# 1_AMS_Input_Stage.net
KiCad netlist of a schematic drawn in Altium Designer
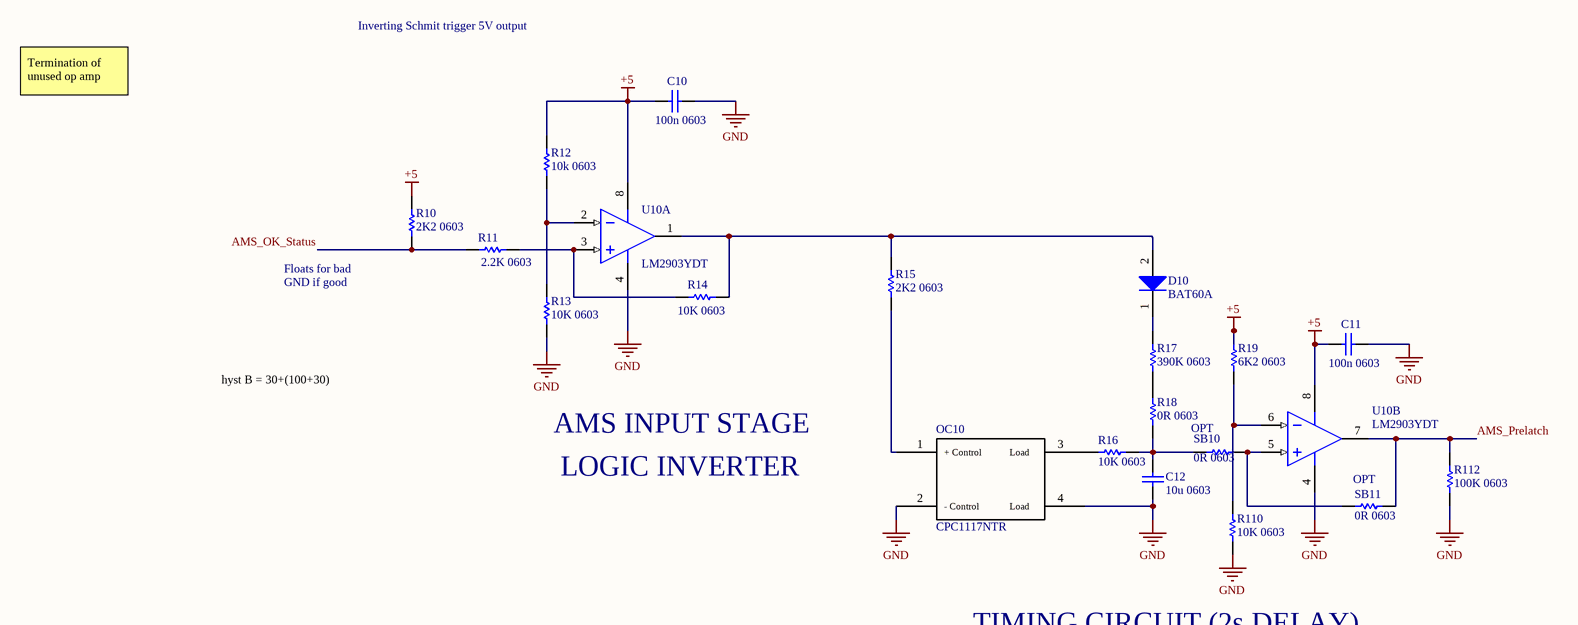
[diagram p0: [1] AMS_Input_Stage.SchDoc]

(export (version "E")
  (design (tool "Eeschema 10.0.6"))
  (components
    (comp (ref "C10")
      (value "100n 0603")
      (footprint "CAPC0603(1608)100_M")
      (description "Capacitor")
      (fields (field (name "PUBLISHER") "Altium Limited"))
      (libsource (lib "Miscellaneous Devices") (part "Cap"))
    )
    (comp (ref "C11")
      (value "100n 0603")
      (footprint "CAPC0603(1608)100_M")
      (description "Capacitor")
      (fields (field (name "PUBLISHER") "Altium Limited"))
      (libsource (lib "Miscellaneous Devices") (part "Cap"))
    )
    (comp (ref "C12")
      (value "10u 0603")
      (footprint "CAPC0603(1608)100_M")
      (description "Capacitor")
      (fields (field (name "PUBLISHER") "Altium Limited"))
      (libsource (lib "Miscellaneous Devices") (part "Cap"))
    )
    (comp (ref "D10")
      (value "BAT60A")
      (footprint "INF-SOD323_V")
      (description "Silicon Schottky Diode, -55 to 85 degC, SOD323, Reel, Green")
      (fields (field (name "MANUFACTURER") "Infineon"))
      (libsource (lib "Altium Content Vault") (part "INF-D_K1A2-2"))
    )
    (comp (ref "OC10")
      (value "CPC1117NTR")
      (footprint "SOP-4 (CPC1117NTR)")
      (libsource (lib "Schematic_Library_AMS_IMD") (part "CPC1117NTR"))
    )
    (comp (ref "R10")
      (value "2K2 0603")
      (footprint "CAPC0603(1608)100_M")
      (description "Resistor")
      (fields (field (name "PUBLISHER") "Altium Limited"))
      (libsource (lib "Miscellaneous Devices") (part "Res1"))
    )
    (comp (ref "R11")
      (value "2.2K 0603")
      (footprint "CAPC0603(1608)100_M")
      (description "Resistor")
      (fields (field (name "PUBLISHER") "Altium Limited"))
      (libsource (lib "Miscellaneous Devices") (part "Res1"))
    )
    (comp (ref "R12")
      (value "10k 0603")
      (footprint "CAPC0603(1608)100_M")
      (description "Resistor")
      (fields (field (name "PUBLISHER") "Altium Limited"))
      (libsource (lib "Miscellaneous Devices") (part "Res1"))
    )
    (comp (ref "R13")
      (value "10K 0603")
      (footprint "CAPC0603(1608)100_M")
      (description "Resistor")
      (fields (field (name "PUBLISHER") "Altium Limited"))
      (libsource (lib "Miscellaneous Devices") (part "Res1"))
    )
    (comp (ref "R14")
      (value "10K 0603")
      (footprint "CAPC0603(1608)100_M")
      (description "Resistor")
      (fields (field (name "PUBLISHER") "Altium Limited"))
      (libsource (lib "Miscellaneous Devices") (part "Res1"))
    )
    (comp (ref "R15")
      (value "2K2 0603")
      (footprint "CAPC0603(1608)100_M")
      (description "Resistor")
      (fields (field (name "PUBLISHER") "Altium Limited"))
      (libsource (lib "Miscellaneous Devices") (part "Res1"))
    )
    (comp (ref "R16")
      (value "10K 0603")
      (footprint "CAPC0603(1608)100_M")
      (description "Resistor")
      (fields (field (name "PUBLISHER") "Altium Limited"))
      (libsource (lib "Miscellaneous Devices") (part "Res1"))
    )
    (comp (ref "R17")
      (value "390K 0603")
      (footprint "CAPC0603(1608)100_M")
      (description "Resistor")
      (fields (field (name "PUBLISHER") "Altium Limited"))
      (libsource (lib "Miscellaneous Devices") (part "Res1"))
    )
    (comp (ref "R18")
      (value "0R 0603")
      (footprint "CAPC0603(1608)100_M")
      (description "Resistor")
      (fields (field (name "PUBLISHER") "Altium Limited"))
      (libsource (lib "Miscellaneous Devices") (part "Res1"))
    )
    (comp (ref "R19")
      (value "6K2 0603")
      (footprint "CAPC0603(1608)100_M")
      (description "Resistor")
      (fields (field (name "PUBLISHER") "Altium Limited"))
      (libsource (lib "Miscellaneous Devices") (part "Res1"))
    )
    (comp (ref "R110")
      (value "10K 0603")
      (footprint "CAPC0603(1608)100_M")
      (description "Resistor")
      (fields (field (name "PUBLISHER") "Altium Limited"))
      (libsource (lib "Miscellaneous Devices") (part "Res1"))
    )
    (comp (ref "R112")
      (value "100K 0603")
      (footprint "CAPC0603(1608)100_M")
      (description "Resistor")
      (fields (field (name "PUBLISHER") "Altium Limited"))
      (libsource (lib "Miscellaneous Devices") (part "Res1"))
    )
    (comp (ref "SB10")
      (value "0R 0603")
      (footprint "CAPC0603(1608)100_M")
      (description "Resistor")
      (fields (field (name "PUBLISHER") "Altium Limited"))
      (libsource (lib "Miscellaneous Devices") (part "Res1"))
    )
    (comp (ref "SB11")
      (value "0R 0603")
      (footprint "CAPC0603(1608)100_M")
      (description "Resistor")
      (fields (field (name "PUBLISHER") "Altium Limited"))
      (libsource (lib "Miscellaneous Devices") (part "Res1"))
    )
    (comp (ref "U10")
      (value "LM2903YDT")
      (footprint "ONSC-SOIC-8-751-07_V")
      (fields (field (name "MANUFACTURER") "On Semiconductor") (field (name "PARTNUMBER") "LM2903DR2G"))
      (libsource (lib "Altium Content Vault") (part "ONSC-LM2903X_X93_LMV393_NVC2903-8"))
    )
  )
  (nets
    (net (code "1") (name "+5") (class "Default")
      (node (ref "C10") (pin "1") (pinfunction "1_1") (pintype "passive"))
      (node (ref "C11") (pin "1") (pinfunction "1_1") (pintype "passive"))
      (node (ref "R10") (pin "1") (pinfunction "1_1") (pintype "passive"))
      (node (ref "R12") (pin "2") (pinfunction "2_2") (pintype "passive"))
      (node (ref "R19") (pin "1") (pinfunction "1_1") (pintype "passive"))
      (node (ref "U10") (pin "8") (pinfunction "VCC_8") (pintype "power_in"))
    )
    (net (code "2") (name "/AMS_OK_Status") (class "Default")
      (node (ref "R10") (pin "2") (pinfunction "2_2") (pintype "passive"))
      (node (ref "R11") (pin "1") (pinfunction "1_1") (pintype "passive"))
    )
    (net (code "3") (name "/AMS_Prelatch") (class "Default")
      (node (ref "R112") (pin "1") (pinfunction "1_1") (pintype "passive"))
      (node (ref "SB11") (pin "2") (pinfunction "2_2") (pintype "passive"))
      (node (ref "U10") (pin "7") (pinfunction "OUTB_7") (pintype "open_collector"))
    )
    (net (code "4") (name "GND") (class "Default")
      (node (ref "C10") (pin "2") (pinfunction "2_2") (pintype "passive"))
      (node (ref "C11") (pin "2") (pinfunction "2_2") (pintype "passive"))
      (node (ref "C12") (pin "2") (pinfunction "2_2") (pintype "passive"))
      (node (ref "OC10") (pin "2") (pinfunction "2_2") (pintype "passive"))
      (node (ref "OC10") (pin "4") (pinfunction "4_4") (pintype "passive"))
      (node (ref "R110") (pin "2") (pinfunction "2_2") (pintype "passive"))
      (node (ref "R112") (pin "2") (pinfunction "2_2") (pintype "passive"))
      (node (ref "R13") (pin "1") (pinfunction "1_1") (pintype "passive"))
      (node (ref "U10") (pin "4") (pinfunction "GND_4") (pintype "power_in"))
    )
    (net (code "5") (name "Net-(C12-Pad1)") (class "Default")
      (node (ref "C12") (pin "1") (pinfunction "1_1") (pintype "passive"))
      (node (ref "R16") (pin "2") (pinfunction "2_2") (pintype "passive"))
      (node (ref "R18") (pin "2") (pinfunction "2_2") (pintype "passive"))
      (node (ref "SB10") (pin "1") (pinfunction "1_1") (pintype "passive"))
    )
    (net (code "6") (name "Net-(D10-A)") (class "Default")
      (node (ref "D10") (pin "2") (pinfunction "A_2") (pintype "passive"))
      (node (ref "R14") (pin "2") (pinfunction "2_2") (pintype "passive"))
      (node (ref "R15") (pin "1") (pinfunction "1_1") (pintype "passive"))
      (node (ref "U10") (pin "1") (pinfunction "OUTA_1") (pintype "open_collector"))
    )
    (net (code "7") (name "Net-(D10-K)") (class "Default")
      (node (ref "D10") (pin "1") (pinfunction "K_1") (pintype "passive"))
      (node (ref "R17") (pin "1") (pinfunction "1_1") (pintype "passive"))
    )
    (net (code "8") (name "Net-(OC10-Pad1)") (class "Default")
      (node (ref "OC10") (pin "1") (pinfunction "1_1") (pintype "passive"))
      (node (ref "R15") (pin "2") (pinfunction "2_2") (pintype "passive"))
    )
    (net (code "9") (name "Net-(OC10-Pad3)") (class "Default")
      (node (ref "OC10") (pin "3") (pinfunction "3_3") (pintype "passive"))
      (node (ref "R16") (pin "1") (pinfunction "1_1") (pintype "passive"))
    )
    (net (code "10") (name "Net-(R17-Pad2)") (class "Default")
      (node (ref "R17") (pin "2") (pinfunction "2_2") (pintype "passive"))
      (node (ref "R18") (pin "1") (pinfunction "1_1") (pintype "passive"))
    )
    (net (code "11") (name "Net-(U10A-INA+)") (class "Default")
      (node (ref "R11") (pin "2") (pinfunction "2_2") (pintype "passive"))
      (node (ref "R14") (pin "1") (pinfunction "1_1") (pintype "passive"))
      (node (ref "U10") (pin "3") (pinfunction "INA+_3") (pintype "input"))
    )
    (net (code "12") (name "Net-(U10A-INA-)") (class "Default")
      (node (ref "R12") (pin "1") (pinfunction "1_1") (pintype "passive"))
      (node (ref "R13") (pin "2") (pinfunction "2_2") (pintype "passive"))
      (node (ref "U10") (pin "2") (pinfunction "INA-_2") (pintype "input"))
    )
    (net (code "13") (name "Net-(U10B-INB+)") (class "Default")
      (node (ref "SB10") (pin "2") (pinfunction "2_2") (pintype "passive"))
      (node (ref "SB11") (pin "1") (pinfunction "1_1") (pintype "passive"))
      (node (ref "U10") (pin "5") (pinfunction "INB+_5") (pintype "input"))
    )
    (net (code "14") (name "Net-(U10B-INB-)") (class "Default")
      (node (ref "R110") (pin "1") (pinfunction "1_1") (pintype "passive"))
      (node (ref "R19") (pin "2") (pinfunction "2_2") (pintype "passive"))
      (node (ref "U10") (pin "6") (pinfunction "INB-_6") (pintype "input"))
    )
  )
)
